# 2uprava6.net
KiCad netlist of a schematic drawn in EAGLE
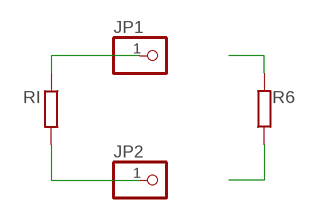
[diagram p0: schematic, sheet 1]

(export (version "E")
  (design (tool "Eeschema 10.0.6"))
  (components
    (comp (ref "JP1")
      (value "PINHD-1X1")
      (footprint "eagle-import:1X01")
      (libsource (lib "eagle-import") (part "PINHD-1X1"))
    )
    (comp (ref "JP2")
      (value "PINHD-1X1")
      (footprint "eagle-import:1X01")
      (libsource (lib "eagle-import") (part "PINHD-1X1"))
    )
    (comp (ref "R6")
      (value "200R")
      (footprint "eagle-import:0204_7")
      (libsource (lib "eagle-import") (part "R-EU_0204/7"))
    )
    (comp (ref "RI")
      (value "570R")
      (footprint "eagle-import:0204_7")
      (libsource (lib "eagle-import") (part "R-EU_0204/7"))
    )
  )
  (nets
    (net (code "1") (name "Net-(JP1-Pad1)") (class "Default")
      (node (ref "JP1") (pin "1") (pinfunction "1_1") (pintype "passive"))
      (node (ref "RI") (pin "1") (pinfunction "1_1") (pintype "passive"))
    )
    (net (code "2") (name "Net-(JP2-Pad1)") (class "Default")
      (node (ref "JP2") (pin "1") (pinfunction "1_1") (pintype "passive"))
      (node (ref "RI") (pin "2") (pinfunction "2_2") (pintype "passive"))
    )
    (net (code "3") (name "unconnected-(R6-Pad1)") (class "Default")
      (node (ref "R6") (pin "1") (pinfunction "1_1") (pintype "passive"))
    )
    (net (code "4") (name "unconnected-(R6-Pad2)") (class "Default")
      (node (ref "R6") (pin "2") (pinfunction "2_2") (pintype "passive"))
    )
  )
)
